# AltiumScheme.net
KiCad netlist of a schematic drawn in Altium Designer
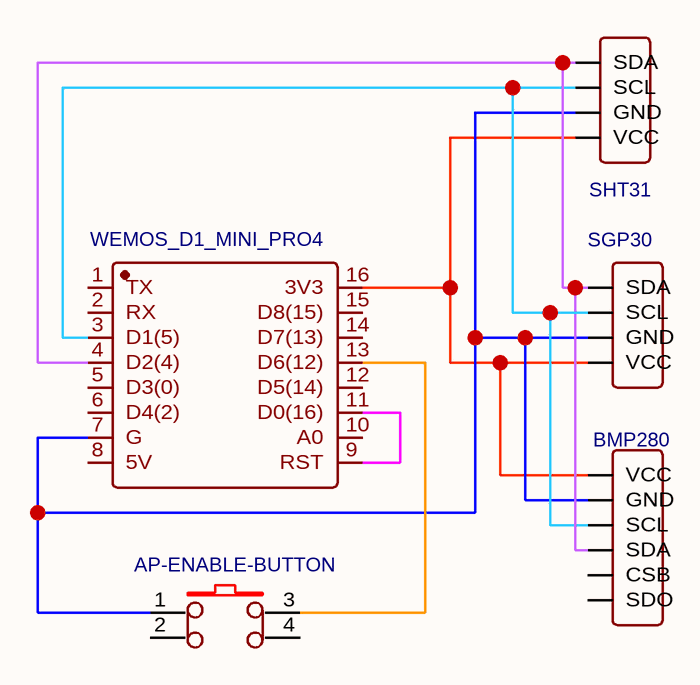
[diagram p0: AltiumScheme.schdoc]

(export (version "E")
  (design (tool "Eeschema 10.0.6"))
  (components
    (comp (ref "AP-ENABLE-BUTTON")
      (value "button6*6*8.5")
      (fields (field (name "BOM_SUPPLIER PART") "C59980"))
      (libsource (lib "altium-import") (part "root_0_button6*6*8.5_"))
    )
    (comp (ref "BMP280")
      (value "HDR-F-2.54_1x6")
      (fields (field (name "BOM_SUPPLIER PART") "C40877") (field (name "CONTRIBUTOR") "LCEDA_Lib"))
      (libsource (lib "altium-import") (part "root_0_HDR-F-2.54_1x6_"))
    )
    (comp (ref "SGP30")
      (value "HDR-F-2.54_1x4")
      (fields (field (name "BOM_SUPPLIER PART") "C225501") (field (name "CONTRIBUTOR") "LCEDA_Lib"))
      (libsource (lib "altium-import") (part "root_0_HDR-F-2.54_1x4_"))
    )
    (comp (ref "SHT31")
      (value "HDR-F-2.54_1x4")
      (fields (field (name "BOM_SUPPLIER PART") "C225501") (field (name "CONTRIBUTOR") "LCEDA_Lib"))
      (libsource (lib "altium-import") (part "root_0_HDR-F-2.54_1x4_"))
    )
    (comp (ref "U1")
      (value "WEMOS_D1_MINI_PRO4")
      (fields
        (field (name "BOM_SUPPLIER PART") "C2837266")
        (field (name "BOM_MANUFACTURER PART") "Wemos_D1_mini_Pro4")
        (field (name "CONTRIBUTOR") "LCSC")
      )
      (libsource (lib "altium-import") (part "root_0_WEMOS_D1_MINI_PRO4_"))
    )
  )
  (nets
    (net (code "1") (name "Net-(BMP280-GND)") (class "Default")
      (node (ref "AP-ENABLE-BUTTON") (pin "1") (pinfunction "1_1") (pintype "passive"))
      (node (ref "BMP280") (pin "2") (pinfunction "GND_2") (pintype "passive"))
      (node (ref "SGP30") (pin "3") (pinfunction "GND_3") (pintype "passive"))
      (node (ref "SHT31") (pin "3") (pinfunction "GND_3") (pintype "passive"))
      (node (ref "U1") (pin "7") (pinfunction "G_7") (pintype "passive"))
    )
    (net (code "2") (name "Net-(BMP280-SCL)") (class "Default")
      (node (ref "BMP280") (pin "3") (pinfunction "SCL_3") (pintype "passive"))
      (node (ref "SGP30") (pin "2") (pinfunction "SCL_2") (pintype "passive"))
      (node (ref "SHT31") (pin "2") (pinfunction "SCL_2") (pintype "passive"))
      (node (ref "U1") (pin "3") (pinfunction "D1(5)_3") (pintype "passive"))
    )
    (net (code "3") (name "Net-(BMP280-SDA)") (class "Default")
      (node (ref "BMP280") (pin "4") (pinfunction "SDA_4") (pintype "passive"))
      (node (ref "SGP30") (pin "1") (pinfunction "SDA_1") (pintype "passive"))
      (node (ref "SHT31") (pin "1") (pinfunction "SDA_1") (pintype "passive"))
      (node (ref "U1") (pin "4") (pinfunction "D2(4)_4") (pintype "passive"))
    )
    (net (code "4") (name "Net-(BMP280-VCC)") (class "Default")
      (node (ref "BMP280") (pin "1") (pinfunction "VCC_1") (pintype "passive"))
      (node (ref "SGP30") (pin "4") (pinfunction "VCC_4") (pintype "passive"))
      (node (ref "SHT31") (pin "4") (pinfunction "VCC_4") (pintype "passive"))
      (node (ref "U1") (pin "16") (pinfunction "3V3_16") (pintype "passive"))
    )
    (net (code "5") (name "Net-(U1-D0(16))") (class "Default")
      (node (ref "U1") (pin "11") (pinfunction "D0(16)_11") (pintype "passive"))
      (node (ref "U1") (pin "9") (pinfunction "RST_9") (pintype "passive"))
    )
    (net (code "6") (name "Net-(U1-D6(12))") (class "Default")
      (node (ref "AP-ENABLE-BUTTON") (pin "3") (pinfunction "3_3") (pintype "passive"))
      (node (ref "U1") (pin "13") (pinfunction "D6(12)_13") (pintype "passive"))
    )
    (net (code "7") (name "unconnected-(AP-ENABLE-BUTTON-Pad2)") (class "Default")
      (node (ref "AP-ENABLE-BUTTON") (pin "2") (pinfunction "2_2") (pintype "passive"))
    )
    (net (code "8") (name "unconnected-(AP-ENABLE-BUTTON-Pad4)") (class "Default")
      (node (ref "AP-ENABLE-BUTTON") (pin "4") (pinfunction "4_4") (pintype "passive"))
    )
    (net (code "9") (name "unconnected-(BMP280-CSB-Pad5)") (class "Default")
      (node (ref "BMP280") (pin "5") (pinfunction "CSB_5") (pintype "passive"))
    )
    (net (code "10") (name "unconnected-(BMP280-SDO-Pad6)") (class "Default")
      (node (ref "BMP280") (pin "6") (pinfunction "SDO_6") (pintype "passive"))
    )
    (net (code "11") (name "unconnected-(U1-5V-Pad8)") (class "Default")
      (node (ref "U1") (pin "8") (pinfunction "5V_8") (pintype "passive"))
    )
    (net (code "12") (name "unconnected-(U1-A0-Pad10)") (class "Default")
      (node (ref "U1") (pin "10") (pinfunction "A0_10") (pintype "passive"))
    )
    (net (code "13") (name "unconnected-(U1-D3(0)-Pad5)") (class "Default")
      (node (ref "U1") (pin "5") (pinfunction "D3(0)_5") (pintype "passive"))
    )
    (net (code "14") (name "unconnected-(U1-D4(2)-Pad6)") (class "Default")
      (node (ref "U1") (pin "6") (pinfunction "D4(2)_6") (pintype "passive"))
    )
    (net (code "15") (name "unconnected-(U1-D5(14)-Pad12)") (class "Default")
      (node (ref "U1") (pin "12") (pinfunction "D5(14)_12") (pintype "passive"))
    )
    (net (code "16") (name "unconnected-(U1-D7(13)-Pad14)") (class "Default")
      (node (ref "U1") (pin "14") (pinfunction "D7(13)_14") (pintype "passive"))
    )
    (net (code "17") (name "unconnected-(U1-D8(15)-Pad15)") (class "Default")
      (node (ref "U1") (pin "15") (pinfunction "D8(15)_15") (pintype "passive"))
    )
    (net (code "18") (name "unconnected-(U1-RX-Pad2)") (class "Default")
      (node (ref "U1") (pin "2") (pinfunction "RX_2") (pintype "passive"))
    )
    (net (code "19") (name "unconnected-(U1-TX-Pad1)") (class "Default")
      (node (ref "U1") (pin "1") (pinfunction "TX_1") (pintype "passive"))
    )
  )
)
